# clock.net
KiCad netlist of a schematic drawn in EAGLE
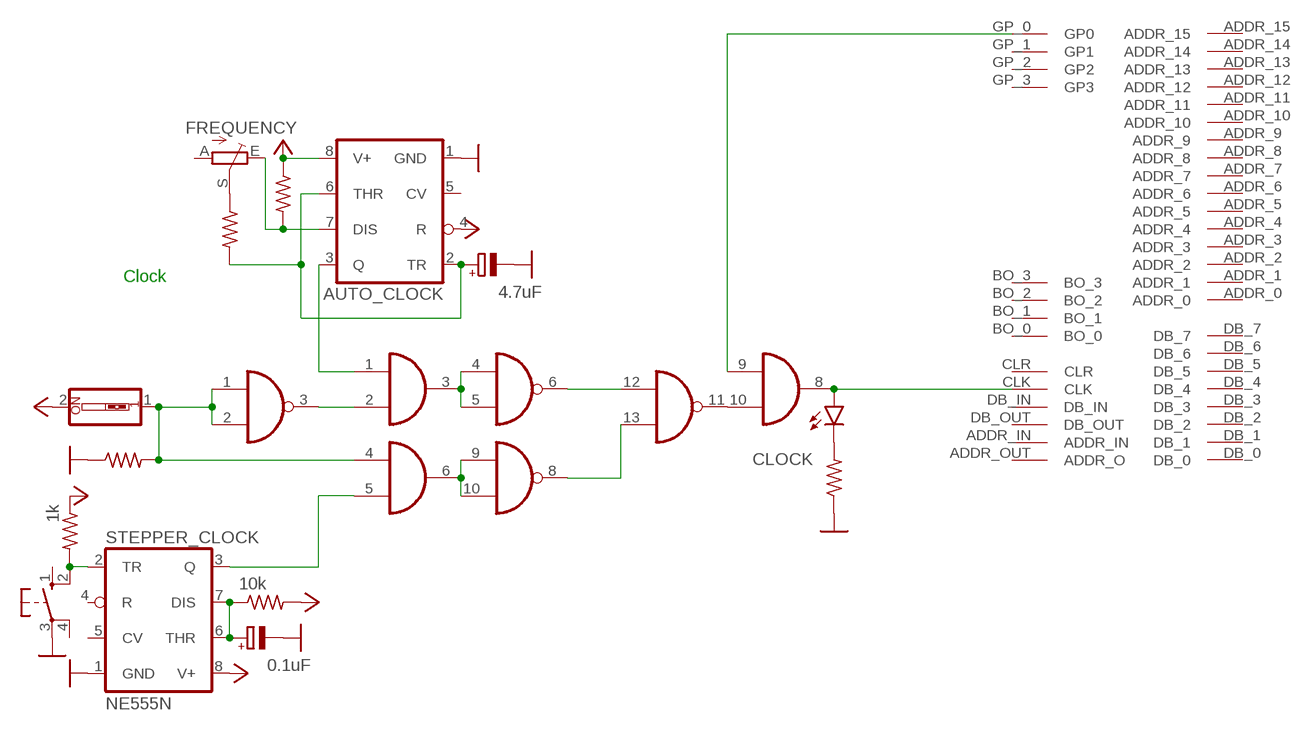
[diagram p0: schematic, sheet 1]

(export (version "E")
  (design (tool "Eeschema 10.0.6"))
  (components
    (comp (ref "AND_GATE_")
      (value "74LS08N")
      (footprint "eagle-import:DIL14")
      (libsource (lib "eagle-import") (part "7408NLS"))
    )
    (comp (ref "AUTO_CLOCK")
      (value "NE555N")
      (footprint "eagle-import:DIL08")
      (libsource (lib "eagle-import") (part "555NNE"))
    )
    (comp (ref "C1")
      (value "4.7uF")
      (footprint "eagle-import:E2-5")
      (libsource (lib "eagle-import") (part "CPOL-EUE2-5"))
    )
    (comp (ref "C2")
      (value "0.1uF")
      (footprint "eagle-import:E2-5")
      (libsource (lib "eagle-import") (part "CPOL-EUE2-5"))
    )
    (comp (ref "CLK_MODE")
      (value "SWITCH")
      (footprint "eagle-import:EDG-01")
      (libsource (lib "eagle-import") (part "SW_DIP-1"))
    )
    (comp (ref "CLK_TRIGGER")
      (value "SWITCH")
      (footprint "eagle-import:B3F-10XX")
      (fields (field (name "MPN") "B3F-1000"))
      (libsource (lib "eagle-import") (part "10-XX"))
    )
    (comp (ref "CLOCK")
      (value "Yellow")
      (footprint "eagle-import:LED5MM")
      (libsource (lib "eagle-import") (part "LED5MM"))
    )
    (comp (ref "FREQUENCY")
      (value "100k")
      (footprint "eagle-import:RJ9W")
      (libsource (lib "eagle-import") (part "TRIM_EU-RJ9W"))
    )
    (comp (ref "NAND")
      (value "74ACT00N")
      (footprint "eagle-import:DIL14")
      (libsource (lib "eagle-import") (part "7400NACT"))
    )
    (comp (ref "R1")
      (value "1k")
      (footprint "eagle-import:0204_7")
      (libsource (lib "eagle-import") (part "R-US_0204/7"))
    )
    (comp (ref "R2")
      (value "1k")
      (footprint "eagle-import:0204_7")
      (libsource (lib "eagle-import") (part "R-US_0204/7"))
    )
    (comp (ref "R3")
      (value "10k")
      (footprint "eagle-import:0204_7")
      (libsource (lib "eagle-import") (part "R-US_0204/7"))
    )
    (comp (ref "R4")
      (value "220")
      (footprint "eagle-import:0204_7")
      (libsource (lib "eagle-import") (part "R-US_0204/7"))
    )
    (comp (ref "R5")
      (value "~220")
      (footprint "eagle-import:0204_7")
      (libsource (lib "eagle-import") (part "R-US_0204/7"))
    )
    (comp (ref "R6")
      (value "220")
      (footprint "eagle-import:0204_7")
      (libsource (lib "eagle-import") (part "R-US_0204/7"))
    )
    (comp (ref "STEPPER_CLOCK")
      (value "NE555N")
      (footprint "eagle-import:DIL08")
      (libsource (lib "eagle-import") (part "555NNE"))
    )
    (comp (ref "U$1")
      (value "BACKPLATE_INTERFACEEDGE_FINGER")
      (footprint "eagle-import:BACK_INTERFACE-FOOT")
      (libsource (lib "eagle-import") (part "BACKPLATE_INTERFACEEDGE_FINGER"))
    )
  )
  (nets
    (net (code "1") (name "GND") (class "Default")
      (node (ref "AUTO_CLOCK") (pin "1") (pinfunction "GND_1") (pintype "power_in"))
      (node (ref "C1") (pin "-") (pinfunction "-_-") (pintype "passive"))
      (node (ref "C2") (pin "-") (pinfunction "-_-") (pintype "passive"))
      (node (ref "CLK_TRIGGER") (pin "3") (pinfunction "P_3") (pintype "passive"))
      (node (ref "R4") (pin "1") (pinfunction "1_1") (pintype "passive"))
      (node (ref "R5") (pin "1") (pinfunction "1_1") (pintype "passive"))
      (node (ref "STEPPER_CLOCK") (pin "1") (pinfunction "GND_1") (pintype "power_in"))
    )
    (net (code "2") (name "Net-(AND_GATE_A-I0)") (class "Default")
      (node (ref "AND_GATE_") (pin "1") (pinfunction "I0_1") (pintype "input"))
      (node (ref "AUTO_CLOCK") (pin "3") (pinfunction "Q_3") (pintype "output"))
    )
    (net (code "3") (name "Net-(AND_GATE_A-I1)") (class "Default")
      (node (ref "AND_GATE_") (pin "2") (pinfunction "I1_2") (pintype "input"))
      (node (ref "NAND") (pin "3") (pinfunction "O_3") (pintype "output"))
    )
    (net (code "4") (name "Net-(AND_GATE_A-O)") (class "Default")
      (node (ref "AND_GATE_") (pin "3") (pinfunction "O_3") (pintype "output"))
      (node (ref "NAND") (pin "4") (pinfunction "I0_4") (pintype "input"))
      (node (ref "NAND") (pin "5") (pinfunction "I1_5") (pintype "input"))
    )
    (net (code "5") (name "Net-(AND_GATE_B-I0)") (class "Default")
      (node (ref "AND_GATE_") (pin "4") (pinfunction "I0_4") (pintype "input"))
      (node (ref "CLK_MODE") (pin "1") (pinfunction "1_1") (pintype "passive"))
      (node (ref "NAND") (pin "1") (pinfunction "I0_1") (pintype "input"))
      (node (ref "NAND") (pin "2") (pinfunction "I1_2") (pintype "input"))
      (node (ref "R4") (pin "2") (pinfunction "2_2") (pintype "passive"))
    )
    (net (code "6") (name "Net-(AND_GATE_B-I1)") (class "Default")
      (node (ref "AND_GATE_") (pin "5") (pinfunction "I1_5") (pintype "input"))
      (node (ref "STEPPER_CLOCK") (pin "3") (pinfunction "Q_3") (pintype "output"))
    )
    (net (code "7") (name "Net-(AND_GATE_B-O)") (class "Default")
      (node (ref "AND_GATE_") (pin "6") (pinfunction "O_6") (pintype "output"))
      (node (ref "NAND") (pin "10") (pinfunction "I1_10") (pintype "input"))
      (node (ref "NAND") (pin "9") (pinfunction "I0_9") (pintype "input"))
    )
    (net (code "8") (name "Net-(AND_GATE_C-I0)") (class "Default")
      (node (ref "AND_GATE_") (pin "9") (pinfunction "I0_9") (pintype "input"))
      (node (ref "U$1") (pin "GP_0") (pinfunction "GP0_GP_0") (pintype "bidirectional"))
    )
    (net (code "9") (name "Net-(AND_GATE_C-I1)") (class "Default")
      (node (ref "AND_GATE_") (pin "10") (pinfunction "I1_10") (pintype "input"))
      (node (ref "NAND") (pin "11") (pinfunction "O_11") (pintype "output"))
    )
    (net (code "10") (name "Net-(AND_GATE_C-O)") (class "Default")
      (node (ref "AND_GATE_") (pin "8") (pinfunction "O_8") (pintype "output"))
      (node (ref "CLOCK") (pin "A") (pinfunction "A_A") (pintype "passive"))
      (node (ref "U$1") (pin "CLK") (pinfunction "CLK_CLK") (pintype "bidirectional"))
    )
    (net (code "11") (name "Net-(AUTO_CLOCK-DIS)") (class "Default")
      (node (ref "AUTO_CLOCK") (pin "7") (pinfunction "DIS_7") (pintype "input"))
      (node (ref "FREQUENCY") (pin "E") (pinfunction "E_E") (pintype "passive"))
      (node (ref "R1") (pin "2") (pinfunction "2_2") (pintype "passive"))
    )
    (net (code "12") (name "Net-(AUTO_CLOCK-THR)") (class "Default")
      (node (ref "AUTO_CLOCK") (pin "2") (pinfunction "TR_2") (pintype "input"))
      (node (ref "AUTO_CLOCK") (pin "6") (pinfunction "THR_6") (pintype "input"))
      (node (ref "C1") (pin "+") (pinfunction "+_+") (pintype "passive"))
      (node (ref "R6") (pin "2") (pinfunction "2_2") (pintype "passive"))
    )
    (net (code "13") (name "Net-(CLK_TRIGGER-S1)") (class "Default")
      (node (ref "CLK_TRIGGER") (pin "2") (pinfunction "S1_2") (pintype "passive"))
      (node (ref "R2") (pin "2") (pinfunction "2_2") (pintype "passive"))
      (node (ref "STEPPER_CLOCK") (pin "2") (pinfunction "TR_2") (pintype "input"))
    )
    (net (code "14") (name "Net-(CLOCK-C)") (class "Default")
      (node (ref "CLOCK") (pin "K") (pinfunction "C_K") (pintype "passive"))
      (node (ref "R5") (pin "2") (pinfunction "2_2") (pintype "passive"))
    )
    (net (code "15") (name "Net-(FREQUENCY-PadS)") (class "Default")
      (node (ref "FREQUENCY") (pin "S") (pinfunction "S_S") (pintype "passive"))
      (node (ref "R6") (pin "1") (pinfunction "1_1") (pintype "passive"))
    )
    (net (code "16") (name "Net-(NANDB-O)") (class "Default")
      (node (ref "NAND") (pin "12") (pinfunction "I0_12") (pintype "input"))
      (node (ref "NAND") (pin "6") (pinfunction "O_6") (pintype "output"))
    )
    (net (code "17") (name "Net-(NANDC-O)") (class "Default")
      (node (ref "NAND") (pin "13") (pinfunction "I1_13") (pintype "input"))
      (node (ref "NAND") (pin "8") (pinfunction "O_8") (pintype "output"))
    )
    (net (code "18") (name "Net-(STEPPER_CLOCK-DIS)") (class "Default")
      (node (ref "C2") (pin "+") (pinfunction "+_+") (pintype "passive"))
      (node (ref "R3") (pin "1") (pinfunction "1_1") (pintype "passive"))
      (node (ref "STEPPER_CLOCK") (pin "6") (pinfunction "THR_6") (pintype "input"))
      (node (ref "STEPPER_CLOCK") (pin "7") (pinfunction "DIS_7") (pintype "input"))
    )
    (net (code "19") (name "VCC") (class "Default")
      (node (ref "AUTO_CLOCK") (pin "4") (pinfunction "R_4") (pintype "input"))
      (node (ref "AUTO_CLOCK") (pin "8") (pinfunction "V+_8") (pintype "power_in"))
      (node (ref "CLK_MODE") (pin "2") (pinfunction "2_2") (pintype "passive"))
      (node (ref "R1") (pin "1") (pinfunction "1_1") (pintype "passive"))
      (node (ref "R2") (pin "1") (pinfunction "1_1") (pintype "passive"))
      (node (ref "R3") (pin "2") (pinfunction "2_2") (pintype "passive"))
      (node (ref "STEPPER_CLOCK") (pin "8") (pinfunction "V+_8") (pintype "power_in"))
    )
    (net (code "20") (name "unconnected-(AUTO_CLOCK-CV-Pad5)") (class "Default")
      (node (ref "AUTO_CLOCK") (pin "5") (pinfunction "CV_5") (pintype "input"))
    )
    (net (code "21") (name "unconnected-(CLK_TRIGGER-P1-Pad4)") (class "Default")
      (node (ref "CLK_TRIGGER") (pin "4") (pinfunction "P1_4") (pintype "passive"))
    )
    (net (code "22") (name "unconnected-(CLK_TRIGGER-S-Pad1)") (class "Default")
      (node (ref "CLK_TRIGGER") (pin "1") (pinfunction "S_1") (pintype "passive"))
    )
    (net (code "23") (name "unconnected-(FREQUENCY-PadA)") (class "Default")
      (node (ref "FREQUENCY") (pin "A") (pinfunction "A_A") (pintype "passive"))
    )
    (net (code "24") (name "unconnected-(STEPPER_CLOCK-CV-Pad5)") (class "Default")
      (node (ref "STEPPER_CLOCK") (pin "5") (pinfunction "CV_5") (pintype "input"))
    )
    (net (code "25") (name "unconnected-(STEPPER_CLOCK-R-Pad4)") (class "Default")
      (node (ref "STEPPER_CLOCK") (pin "4") (pinfunction "R_4") (pintype "input"))
    )
    (net (code "26") (name "unconnected-(U$1-PadADDR_0)") (class "Default")
      (node (ref "U$1") (pin "ADDR_0") (pinfunction "ADDR_0_ADDR_0") (pintype "bidirectional"))
    )
    (net (code "27") (name "unconnected-(U$1-PadADDR_1)") (class "Default")
      (node (ref "U$1") (pin "ADDR_1") (pinfunction "ADDR_1_ADDR_1") (pintype "bidirectional"))
    )
    (net (code "28") (name "unconnected-(U$1-PadADDR_2)") (class "Default")
      (node (ref "U$1") (pin "ADDR_2") (pinfunction "ADDR_2_ADDR_2") (pintype "bidirectional"))
    )
    (net (code "29") (name "unconnected-(U$1-PadADDR_3)") (class "Default")
      (node (ref "U$1") (pin "ADDR_3") (pinfunction "ADDR_3_ADDR_3") (pintype "bidirectional"))
    )
    (net (code "30") (name "unconnected-(U$1-PadADDR_4)") (class "Default")
      (node (ref "U$1") (pin "ADDR_4") (pinfunction "ADDR_4_ADDR_4") (pintype "bidirectional"))
    )
    (net (code "31") (name "unconnected-(U$1-PadADDR_5)") (class "Default")
      (node (ref "U$1") (pin "ADDR_5") (pinfunction "ADDR_5_ADDR_5") (pintype "bidirectional"))
    )
    (net (code "32") (name "unconnected-(U$1-PadADDR_6)") (class "Default")
      (node (ref "U$1") (pin "ADDR_6") (pinfunction "ADDR_6_ADDR_6") (pintype "bidirectional"))
    )
    (net (code "33") (name "unconnected-(U$1-PadADDR_7)") (class "Default")
      (node (ref "U$1") (pin "ADDR_7") (pinfunction "ADDR_7_ADDR_7") (pintype "bidirectional"))
    )
    (net (code "34") (name "unconnected-(U$1-PadADDR_8)") (class "Default")
      (node (ref "U$1") (pin "ADDR_8") (pinfunction "ADDR_8_ADDR_8") (pintype "bidirectional"))
    )
    (net (code "35") (name "unconnected-(U$1-PadADDR_9)") (class "Default")
      (node (ref "U$1") (pin "ADDR_9") (pinfunction "ADDR_9_ADDR_9") (pintype "bidirectional"))
    )
    (net (code "36") (name "unconnected-(U$1-PadADDR_10)") (class "Default")
      (node (ref "U$1") (pin "ADDR_10") (pinfunction "ADDR_10_ADDR_10") (pintype "bidirectional"))
    )
    (net (code "37") (name "unconnected-(U$1-PadADDR_11)") (class "Default")
      (node (ref "U$1") (pin "ADDR_11") (pinfunction "ADDR_11_ADDR_11") (pintype "bidirectional"))
    )
    (net (code "38") (name "unconnected-(U$1-PadADDR_12)") (class "Default")
      (node (ref "U$1") (pin "ADDR_12") (pinfunction "ADDR_12_ADDR_12") (pintype "bidirectional"))
    )
    (net (code "39") (name "unconnected-(U$1-PadADDR_13)") (class "Default")
      (node (ref "U$1") (pin "ADDR_13") (pinfunction "ADDR_13_ADDR_13") (pintype "bidirectional"))
    )
    (net (code "40") (name "unconnected-(U$1-PadADDR_14)") (class "Default")
      (node (ref "U$1") (pin "ADDR_14") (pinfunction "ADDR_14_ADDR_14") (pintype "bidirectional"))
    )
    (net (code "41") (name "unconnected-(U$1-PadADDR_15)") (class "Default")
      (node (ref "U$1") (pin "ADDR_15") (pinfunction "ADDR_15_ADDR_15") (pintype "bidirectional"))
    )
    (net (code "42") (name "unconnected-(U$1-PadADDR_IN)") (class "Default")
      (node (ref "U$1") (pin "ADDR_IN") (pinfunction "ADDR_IN_ADDR_IN") (pintype "bidirectional"))
    )
    (net (code "43") (name "unconnected-(U$1-PadBO_0)") (class "Default")
      (node (ref "U$1") (pin "BO_0") (pinfunction "BO_0_BO_0") (pintype "bidirectional"))
    )
    (net (code "44") (name "unconnected-(U$1-PadBO_1)") (class "Default")
      (node (ref "U$1") (pin "BO_1") (pinfunction "BO_1_BO_1") (pintype "bidirectional"))
    )
    (net (code "45") (name "unconnected-(U$1-PadBO_2)") (class "Default")
      (node (ref "U$1") (pin "BO_2") (pinfunction "BO_2_BO_2") (pintype "bidirectional"))
    )
    (net (code "46") (name "unconnected-(U$1-PadBO_3)") (class "Default")
      (node (ref "U$1") (pin "BO_3") (pinfunction "BO_3_BO_3") (pintype "bidirectional"))
    )
    (net (code "47") (name "unconnected-(U$1-PadCLR)") (class "Default")
      (node (ref "U$1") (pin "CLR") (pinfunction "CLR_CLR") (pintype "bidirectional"))
    )
    (net (code "48") (name "unconnected-(U$1-PadDB_0)") (class "Default")
      (node (ref "U$1") (pin "DB_0") (pinfunction "DB_0_DB_0") (pintype "bidirectional"))
    )
    (net (code "49") (name "unconnected-(U$1-PadDB_1)") (class "Default")
      (node (ref "U$1") (pin "DB_1") (pinfunction "DB_1_DB_1") (pintype "bidirectional"))
    )
    (net (code "50") (name "unconnected-(U$1-PadDB_2)") (class "Default")
      (node (ref "U$1") (pin "DB_2") (pinfunction "DB_2_DB_2") (pintype "bidirectional"))
    )
    (net (code "51") (name "unconnected-(U$1-PadDB_3)") (class "Default")
      (node (ref "U$1") (pin "DB_3") (pinfunction "DB_3_DB_3") (pintype "bidirectional"))
    )
    (net (code "52") (name "unconnected-(U$1-PadDB_4)") (class "Default")
      (node (ref "U$1") (pin "DB_4") (pinfunction "DB_4_DB_4") (pintype "bidirectional"))
    )
    (net (code "53") (name "unconnected-(U$1-PadDB_5)") (class "Default")
      (node (ref "U$1") (pin "DB_5") (pinfunction "DB_5_DB_5") (pintype "bidirectional"))
    )
    (net (code "54") (name "unconnected-(U$1-PadDB_6)") (class "Default")
      (node (ref "U$1") (pin "DB_6") (pinfunction "DB_6_DB_6") (pintype "bidirectional"))
    )
    (net (code "55") (name "unconnected-(U$1-PadDB_7)") (class "Default")
      (node (ref "U$1") (pin "DB_7") (pinfunction "DB_7_DB_7") (pintype "bidirectional"))
    )
    (net (code "56") (name "unconnected-(U$1-PadDB_IN)") (class "Default")
      (node (ref "U$1") (pin "DB_IN") (pinfunction "DB_IN_DB_IN") (pintype "bidirectional"))
    )
    (net (code "57") (name "unconnected-(U$1-PadDB_OUT)") (class "Default")
      (node (ref "U$1") (pin "DB_OUT") (pinfunction "DB_OUT_DB_OUT") (pintype "bidirectional"))
    )
    (net (code "58") (name "unconnected-(U$1A-ADDR_O-PadADDR_OUT)") (class "Default")
      (node (ref "U$1") (pin "ADDR_OUT") (pinfunction "ADDR_O_ADDR_OUT") (pintype "bidirectional"))
    )
    (net (code "59") (name "unconnected-(U$1A-GP1-PadGP_1)") (class "Default")
      (node (ref "U$1") (pin "GP_1") (pinfunction "GP1_GP_1") (pintype "bidirectional"))
    )
    (net (code "60") (name "unconnected-(U$1A-GP2-PadGP_2)") (class "Default")
      (node (ref "U$1") (pin "GP_2") (pinfunction "GP2_GP_2") (pintype "bidirectional"))
    )
    (net (code "61") (name "unconnected-(U$1A-GP3-PadGP_3)") (class "Default")
      (node (ref "U$1") (pin "GP_3") (pinfunction "GP3_GP_3") (pintype "bidirectional"))
    )
  )
)
